# titan.net
KiCad netlist of a schematic drawn in EAGLE
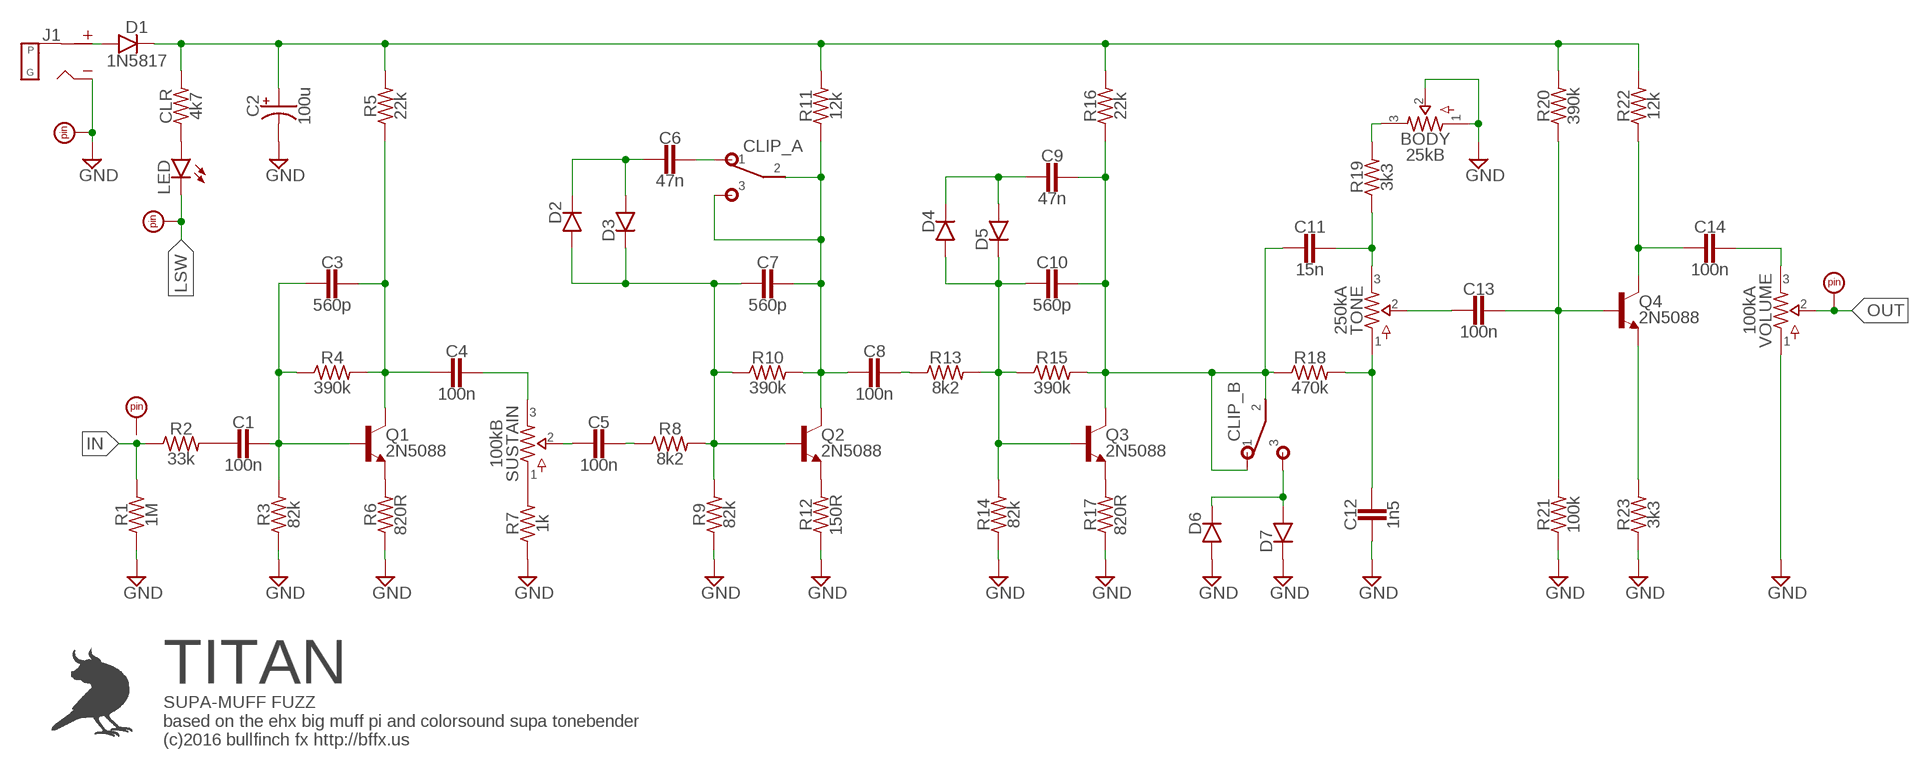
[diagram p0: schematic, sheet 1]

(export (version "E")
  (design (tool "Eeschema 10.0.6"))
  (components
    (comp (ref "BODY")
      (value "25kB")
      (footprint "eagle-import:16MM")
      (libsource (lib "eagle-import") (part "POTS16MM"))
    )
    (comp (ref "C1")
      (value "100n")
      (footprint "eagle-import:050X030_025_2")
      (libsource (lib "eagle-import") (part "CER/FILM2"))
    )
    (comp (ref "C2")
      (value "100u")
      (footprint "eagle-import:050_020_1")
      (libsource (lib "eagle-import") (part "0501"))
    )
    (comp (ref "C3")
      (value "560p")
      (footprint "eagle-import:050X030_025_2")
      (libsource (lib "eagle-import") (part "CER/FILM2"))
    )
    (comp (ref "C4")
      (value "100n")
      (footprint "eagle-import:050X030_025_2")
      (libsource (lib "eagle-import") (part "CER/FILM2"))
    )
    (comp (ref "C5")
      (value "100n")
      (footprint "eagle-import:050X030_025_2")
      (libsource (lib "eagle-import") (part "CER/FILM2"))
    )
    (comp (ref "C6")
      (value "47n")
      (footprint "eagle-import:050X030_025_2")
      (libsource (lib "eagle-import") (part "CER/FILM2"))
    )
    (comp (ref "C7")
      (value "560p")
      (footprint "eagle-import:050X030_025_2")
      (libsource (lib "eagle-import") (part "CER/FILM2"))
    )
    (comp (ref "C8")
      (value "100n")
      (footprint "eagle-import:050X030_025_2")
      (libsource (lib "eagle-import") (part "CER/FILM2"))
    )
    (comp (ref "C9")
      (value "47n")
      (footprint "eagle-import:050X030_025_2")
      (libsource (lib "eagle-import") (part "CER/FILM2"))
    )
    (comp (ref "C10")
      (value "560p")
      (footprint "eagle-import:050X030_025_2")
      (libsource (lib "eagle-import") (part "CER/FILM2"))
    )
    (comp (ref "C11")
      (value "15n")
      (footprint "eagle-import:050X030_025_2")
      (libsource (lib "eagle-import") (part "CER/FILM2"))
    )
    (comp (ref "C12")
      (value "1n5")
      (footprint "eagle-import:050X030_025_2")
      (libsource (lib "eagle-import") (part "CER/FILM2"))
    )
    (comp (ref "C13")
      (value "100n")
      (footprint "eagle-import:050X030_025_2")
      (libsource (lib "eagle-import") (part "CER/FILM2"))
    )
    (comp (ref "C14")
      (value "100n")
      (footprint "eagle-import:050X030_025_2")
      (libsource (lib "eagle-import") (part "CER/FILM2"))
    )
    (comp (ref "CLIP")
      (value "DPDTPADS")
      (footprint "eagle-import:DPDT_PADS")
      (libsource (lib "eagle-import") (part "DPDTPADS"))
    )
    (comp (ref "CLR")
      (value "4k7")
      (footprint "eagle-import:R0207_3")
      (libsource (lib "eagle-import") (part "R_.3B"))
    )
    (comp (ref "D1")
      (value "1N5817")
      (footprint "eagle-import:DO41-3")
      (libsource (lib "eagle-import") (part "DO41.3"))
    )
    (comp (ref "D2")
      (value "DO35.2")
      (footprint "eagle-import:DO35-2")
      (libsource (lib "eagle-import") (part "DO35.2"))
    )
    (comp (ref "D3")
      (value "DO35.2")
      (footprint "eagle-import:DO35-2")
      (libsource (lib "eagle-import") (part "DO35.2"))
    )
    (comp (ref "D4")
      (value "DO35.2")
      (footprint "eagle-import:DO35-2")
      (libsource (lib "eagle-import") (part "DO35.2"))
    )
    (comp (ref "D5")
      (value "DO35.2")
      (footprint "eagle-import:DO35-2")
      (libsource (lib "eagle-import") (part "DO35.2"))
    )
    (comp (ref "D6")
      (value "DO35.2")
      (footprint "eagle-import:DO35-2")
      (libsource (lib "eagle-import") (part "DO35.2"))
    )
    (comp (ref "D7")
      (value "DO35.2")
      (footprint "eagle-import:DO35-2")
      (libsource (lib "eagle-import") (part "DO35.2"))
    )
    (comp (ref "GND")
      (value "PADRND")
      (footprint "eagle-import:ROUND")
      (libsource (lib "eagle-import") (part "PADRND"))
    )
    (comp (ref "IN")
      (value "PADSQR")
      (footprint "eagle-import:SQUARE")
      (libsource (lib "eagle-import") (part "PADSQR"))
    )
    (comp (ref "J1")
      (value "DC_MONO")
      (footprint "eagle-import:DC")
      (libsource (lib "eagle-import") (part "DC_MONO"))
    )
    (comp (ref "LED")
      (value "LEDA")
      (footprint "eagle-import:3MM_A")
      (libsource (lib "eagle-import") (part "LEDA"))
    )
    (comp (ref "LSW")
      (value "PADSQR")
      (footprint "eagle-import:SQUARE")
      (libsource (lib "eagle-import") (part "PADSQR"))
    )
    (comp (ref "OUT")
      (value "PADSQR")
      (footprint "eagle-import:SQUARE")
      (libsource (lib "eagle-import") (part "PADSQR"))
    )
    (comp (ref "Q1")
      (value "2N5088")
      (footprint "eagle-import:TO92-")
      (libsource (lib "eagle-import") (part "2N5088"))
    )
    (comp (ref "Q2")
      (value "2N5088")
      (footprint "eagle-import:TO92-")
      (libsource (lib "eagle-import") (part "2N5088"))
    )
    (comp (ref "Q3")
      (value "2N5088")
      (footprint "eagle-import:TO92-")
      (libsource (lib "eagle-import") (part "2N5088"))
    )
    (comp (ref "Q4")
      (value "2N5088")
      (footprint "eagle-import:TO92-")
      (libsource (lib "eagle-import") (part "2N5088"))
    )
    (comp (ref "R1")
      (value "1M")
      (footprint "eagle-import:R0207_3")
      (libsource (lib "eagle-import") (part "R_.3B"))
    )
    (comp (ref "R2")
      (value "33k")
      (footprint "eagle-import:R0207_3")
      (libsource (lib "eagle-import") (part "R_.3B"))
    )
    (comp (ref "R3")
      (value "82k")
      (footprint "eagle-import:R0207_3")
      (libsource (lib "eagle-import") (part "R_.3B"))
    )
    (comp (ref "R4")
      (value "390k")
      (footprint "eagle-import:R0207_3")
      (libsource (lib "eagle-import") (part "R_.3B"))
    )
    (comp (ref "R5")
      (value "22k")
      (footprint "eagle-import:R0207_3")
      (libsource (lib "eagle-import") (part "R_.3B"))
    )
    (comp (ref "R6")
      (value "820R")
      (footprint "eagle-import:R0207_3")
      (libsource (lib "eagle-import") (part "R_.3B"))
    )
    (comp (ref "R7")
      (value "1k")
      (footprint "eagle-import:R0207_3")
      (libsource (lib "eagle-import") (part "R_.3B"))
    )
    (comp (ref "R8")
      (value "8k2")
      (footprint "eagle-import:R0207_3")
      (libsource (lib "eagle-import") (part "R_.3B"))
    )
    (comp (ref "R9")
      (value "82k")
      (footprint "eagle-import:R0207_3")
      (libsource (lib "eagle-import") (part "R_.3B"))
    )
    (comp (ref "R10")
      (value "390k")
      (footprint "eagle-import:R0207_3")
      (libsource (lib "eagle-import") (part "R_.3B"))
    )
    (comp (ref "R11")
      (value "12k")
      (footprint "eagle-import:R0207_3")
      (libsource (lib "eagle-import") (part "R_.3B"))
    )
    (comp (ref "R12")
      (value "150R")
      (footprint "eagle-import:R0207_3")
      (libsource (lib "eagle-import") (part "R_.3B"))
    )
    (comp (ref "R13")
      (value "8k2")
      (footprint "eagle-import:R0207_3")
      (libsource (lib "eagle-import") (part "R_.3B"))
    )
    (comp (ref "R14")
      (value "82k")
      (footprint "eagle-import:R0207_3")
      (libsource (lib "eagle-import") (part "R_.3B"))
    )
    (comp (ref "R15")
      (value "390k")
      (footprint "eagle-import:R0207_3")
      (libsource (lib "eagle-import") (part "R_.3B"))
    )
    (comp (ref "R16")
      (value "22k")
      (footprint "eagle-import:R0207_3")
      (libsource (lib "eagle-import") (part "R_.3B"))
    )
    (comp (ref "R17")
      (value "820R")
      (footprint "eagle-import:R0207_3")
      (libsource (lib "eagle-import") (part "R_.3B"))
    )
    (comp (ref "R18")
      (value "470k")
      (footprint "eagle-import:R0207_3")
      (libsource (lib "eagle-import") (part "R_.3B"))
    )
    (comp (ref "R19")
      (value "3k3")
      (footprint "eagle-import:R0207_3")
      (libsource (lib "eagle-import") (part "R_.3B"))
    )
    (comp (ref "R20")
      (value "390k")
      (footprint "eagle-import:R0207_3")
      (libsource (lib "eagle-import") (part "R_.3B"))
    )
    (comp (ref "R21")
      (value "100k")
      (footprint "eagle-import:R0207_3")
      (libsource (lib "eagle-import") (part "R_.3B"))
    )
    (comp (ref "R22")
      (value "12k")
      (footprint "eagle-import:R0207_3")
      (libsource (lib "eagle-import") (part "R_.3B"))
    )
    (comp (ref "R23")
      (value "3k3")
      (footprint "eagle-import:R0207_3")
      (libsource (lib "eagle-import") (part "R_.3B"))
    )
    (comp (ref "SUSTAIN")
      (value "100kB")
      (footprint "eagle-import:16MM")
      (libsource (lib "eagle-import") (part "POTS16MM"))
    )
    (comp (ref "TONE")
      (value "250kA")
      (footprint "eagle-import:16MM")
      (libsource (lib "eagle-import") (part "POTS16MM"))
    )
    (comp (ref "VOLUME")
      (value "100kA")
      (footprint "eagle-import:16MM")
      (libsource (lib "eagle-import") (part "POTS16MM"))
    )
  )
  (nets
    (net (code "1") (name "GND") (class "Default")
      (node (ref "BODY") (pin "1") (pinfunction "1_1") (pintype "passive"))
      (node (ref "BODY") (pin "2") (pinfunction "2_2") (pintype "passive"))
      (node (ref "C12") (pin "2") (pinfunction "2_2") (pintype "passive"))
      (node (ref "C2") (pin "-") (pinfunction "-_-") (pintype "passive"))
      (node (ref "D6") (pin "A") (pinfunction "A_A") (pintype "passive"))
      (node (ref "D7") (pin "C") (pinfunction "C_C") (pintype "passive"))
      (node (ref "GND") (pin "1") (pinfunction "P$1_1") (pintype "bidirectional"))
      (node (ref "J1") (pin "S") (pinfunction "SLEEVE_S") (pintype "passive"))
      (node (ref "R1") (pin "1") (pinfunction "1_1") (pintype "passive"))
      (node (ref "R12") (pin "1") (pinfunction "1_1") (pintype "passive"))
      (node (ref "R14") (pin "1") (pinfunction "1_1") (pintype "passive"))
      (node (ref "R17") (pin "1") (pinfunction "1_1") (pintype "passive"))
      (node (ref "R21") (pin "1") (pinfunction "1_1") (pintype "passive"))
      (node (ref "R23") (pin "1") (pinfunction "1_1") (pintype "passive"))
      (node (ref "R3") (pin "1") (pinfunction "1_1") (pintype "passive"))
      (node (ref "R6") (pin "1") (pinfunction "1_1") (pintype "passive"))
      (node (ref "R7") (pin "1") (pinfunction "1_1") (pintype "passive"))
      (node (ref "R9") (pin "1") (pinfunction "1_1") (pintype "passive"))
      (node (ref "VOLUME") (pin "1") (pinfunction "1_1") (pintype "passive"))
    )
    (net (code "2") (name "IN") (class "Default")
      (node (ref "R1") (pin "2") (pinfunction "2_2") (pintype "passive"))
      (node (ref "R2") (pin "1") (pinfunction "1_1") (pintype "passive"))
    )
    (net (code "3") (name "LSW") (class "Default")
      (node (ref "LED") (pin "K") (pinfunction "C_K") (pintype "passive"))
      (node (ref "LSW") (pin "1") (pinfunction "P$1_1") (pintype "bidirectional"))
    )
    (net (code "4") (name "Net-(BODY-Pad3)") (class "Default")
      (node (ref "BODY") (pin "3") (pinfunction "3_3") (pintype "passive"))
      (node (ref "R19") (pin "2") (pinfunction "2_2") (pintype "passive"))
    )
    (net (code "5") (name "Net-(C1-Pad2)") (class "Default")
      (node (ref "C1") (pin "2") (pinfunction "2_2") (pintype "passive"))
      (node (ref "R2") (pin "2") (pinfunction "2_2") (pintype "passive"))
    )
    (net (code "6") (name "Net-(C2-Pad+)") (class "Default")
      (node (ref "C2") (pin "+") (pinfunction "+_+") (pintype "passive"))
      (node (ref "CLR") (pin "2") (pinfunction "2_2") (pintype "passive"))
      (node (ref "D1") (pin "C") (pinfunction "C_C") (pintype "passive"))
      (node (ref "R11") (pin "2") (pinfunction "2_2") (pintype "passive"))
      (node (ref "R16") (pin "2") (pinfunction "2_2") (pintype "passive"))
      (node (ref "R20") (pin "2") (pinfunction "2_2") (pintype "passive"))
      (node (ref "R22") (pin "2") (pinfunction "2_2") (pintype "passive"))
      (node (ref "R5") (pin "2") (pinfunction "2_2") (pintype "passive"))
    )
    (net (code "7") (name "Net-(C4-Pad1)") (class "Default")
      (node (ref "C4") (pin "1") (pinfunction "1_1") (pintype "passive"))
      (node (ref "SUSTAIN") (pin "3") (pinfunction "3_3") (pintype "passive"))
    )
    (net (code "8") (name "Net-(C5-Pad1)") (class "Default")
      (node (ref "C5") (pin "1") (pinfunction "1_1") (pintype "passive"))
      (node (ref "R8") (pin "1") (pinfunction "1_1") (pintype "passive"))
    )
    (net (code "9") (name "Net-(C5-Pad2)") (class "Default")
      (node (ref "C5") (pin "2") (pinfunction "2_2") (pintype "passive"))
      (node (ref "SUSTAIN") (pin "2") (pinfunction "2_2") (pintype "passive"))
    )
    (net (code "10") (name "Net-(C6-Pad2)") (class "Default")
      (node (ref "C6") (pin "2") (pinfunction "2_2") (pintype "passive"))
      (node (ref "D2") (pin "C") (pinfunction "C_C") (pintype "passive"))
      (node (ref "D3") (pin "A") (pinfunction "A_A") (pintype "passive"))
    )
    (net (code "11") (name "Net-(C8-Pad1)") (class "Default")
      (node (ref "C8") (pin "1") (pinfunction "1_1") (pintype "passive"))
      (node (ref "R13") (pin "1") (pinfunction "1_1") (pintype "passive"))
    )
    (net (code "12") (name "Net-(C9-Pad2)") (class "Default")
      (node (ref "C9") (pin "2") (pinfunction "2_2") (pintype "passive"))
      (node (ref "D4") (pin "C") (pinfunction "C_C") (pintype "passive"))
      (node (ref "D5") (pin "A") (pinfunction "A_A") (pintype "passive"))
    )
    (net (code "13") (name "Net-(C11-Pad1)") (class "Default")
      (node (ref "C11") (pin "1") (pinfunction "1_1") (pintype "passive"))
      (node (ref "R19") (pin "1") (pinfunction "1_1") (pintype "passive"))
      (node (ref "TONE") (pin "3") (pinfunction "3_3") (pintype "passive"))
    )
    (net (code "14") (name "Net-(C12-Pad1)") (class "Default")
      (node (ref "C12") (pin "1") (pinfunction "1_1") (pintype "passive"))
      (node (ref "R18") (pin "2") (pinfunction "2_2") (pintype "passive"))
      (node (ref "TONE") (pin "1") (pinfunction "1_1") (pintype "passive"))
    )
    (net (code "15") (name "Net-(C13-Pad2)") (class "Default")
      (node (ref "C13") (pin "2") (pinfunction "2_2") (pintype "passive"))
      (node (ref "TONE") (pin "2") (pinfunction "2_2") (pintype "passive"))
    )
    (net (code "16") (name "Net-(C14-Pad1)") (class "Default")
      (node (ref "C14") (pin "1") (pinfunction "1_1") (pintype "passive"))
      (node (ref "VOLUME") (pin "3") (pinfunction "3_3") (pintype "passive"))
    )
    (net (code "17") (name "Net-(CLIPA-1)") (class "Default")
      (node (ref "C6") (pin "1") (pinfunction "1_1") (pintype "passive"))
      (node (ref "CLIP") (pin "P$1") (pinfunction "1_P$1") (pintype "passive"))
    )
    (net (code "18") (name "Net-(CLIPA-2)") (class "Default")
      (node (ref "C7") (pin "1") (pinfunction "1_1") (pintype "passive"))
      (node (ref "C8") (pin "2") (pinfunction "2_2") (pintype "passive"))
      (node (ref "CLIP") (pin "P$2") (pinfunction "2_P$2") (pintype "passive"))
      (node (ref "CLIP") (pin "P$3") (pinfunction "3_P$3") (pintype "passive"))
      (node (ref "Q2") (pin "1") (pinfunction "C_1") (pintype "passive"))
      (node (ref "R10") (pin "2") (pinfunction "2_2") (pintype "passive"))
      (node (ref "R11") (pin "1") (pinfunction "1_1") (pintype "passive"))
    )
    (net (code "19") (name "Net-(CLIPB-1)") (class "Default")
      (node (ref "C10") (pin "1") (pinfunction "1_1") (pintype "passive"))
      (node (ref "C11") (pin "2") (pinfunction "2_2") (pintype "passive"))
      (node (ref "C9") (pin "1") (pinfunction "1_1") (pintype "passive"))
      (node (ref "CLIP") (pin "P$4") (pinfunction "1_P$4") (pintype "passive"))
      (node (ref "CLIP") (pin "P$5") (pinfunction "2_P$5") (pintype "passive"))
      (node (ref "Q3") (pin "1") (pinfunction "C_1") (pintype "passive"))
      (node (ref "R15") (pin "2") (pinfunction "2_2") (pintype "passive"))
      (node (ref "R16") (pin "1") (pinfunction "1_1") (pintype "passive"))
      (node (ref "R18") (pin "1") (pinfunction "1_1") (pintype "passive"))
    )
    (net (code "20") (name "Net-(CLIPB-3)") (class "Default")
      (node (ref "CLIP") (pin "P$6") (pinfunction "3_P$6") (pintype "passive"))
      (node (ref "D6") (pin "C") (pinfunction "C_C") (pintype "passive"))
      (node (ref "D7") (pin "A") (pinfunction "A_A") (pintype "passive"))
    )
    (net (code "21") (name "Net-(CLR-Pad1)") (class "Default")
      (node (ref "CLR") (pin "1") (pinfunction "1_1") (pintype "passive"))
      (node (ref "LED") (pin "A") (pinfunction "A_A") (pintype "passive"))
    )
    (net (code "22") (name "Net-(J1-TIP)") (class "Default")
      (node (ref "D1") (pin "A") (pinfunction "A_A") (pintype "passive"))
      (node (ref "J1") (pin "T") (pinfunction "TIP_T") (pintype "passive"))
    )
    (net (code "23") (name "Net-(Q1-B)") (class "Default")
      (node (ref "C1") (pin "1") (pinfunction "1_1") (pintype "passive"))
      (node (ref "C3") (pin "2") (pinfunction "2_2") (pintype "passive"))
      (node (ref "Q1") (pin "2") (pinfunction "B_2") (pintype "passive"))
      (node (ref "R3") (pin "2") (pinfunction "2_2") (pintype "passive"))
      (node (ref "R4") (pin "1") (pinfunction "1_1") (pintype "passive"))
    )
    (net (code "24") (name "Net-(Q1-C)") (class "Default")
      (node (ref "C3") (pin "1") (pinfunction "1_1") (pintype "passive"))
      (node (ref "C4") (pin "2") (pinfunction "2_2") (pintype "passive"))
      (node (ref "Q1") (pin "1") (pinfunction "C_1") (pintype "passive"))
      (node (ref "R4") (pin "2") (pinfunction "2_2") (pintype "passive"))
      (node (ref "R5") (pin "1") (pinfunction "1_1") (pintype "passive"))
    )
    (net (code "25") (name "Net-(Q1-E)") (class "Default")
      (node (ref "Q1") (pin "3") (pinfunction "E_3") (pintype "passive"))
      (node (ref "R6") (pin "2") (pinfunction "2_2") (pintype "passive"))
    )
    (net (code "26") (name "Net-(Q2-B)") (class "Default")
      (node (ref "C7") (pin "2") (pinfunction "2_2") (pintype "passive"))
      (node (ref "D2") (pin "A") (pinfunction "A_A") (pintype "passive"))
      (node (ref "D3") (pin "C") (pinfunction "C_C") (pintype "passive"))
      (node (ref "Q2") (pin "2") (pinfunction "B_2") (pintype "passive"))
      (node (ref "R10") (pin "1") (pinfunction "1_1") (pintype "passive"))
      (node (ref "R8") (pin "2") (pinfunction "2_2") (pintype "passive"))
      (node (ref "R9") (pin "2") (pinfunction "2_2") (pintype "passive"))
    )
    (net (code "27") (name "Net-(Q2-E)") (class "Default")
      (node (ref "Q2") (pin "3") (pinfunction "E_3") (pintype "passive"))
      (node (ref "R12") (pin "2") (pinfunction "2_2") (pintype "passive"))
    )
    (net (code "28") (name "Net-(Q3-B)") (class "Default")
      (node (ref "C10") (pin "2") (pinfunction "2_2") (pintype "passive"))
      (node (ref "D4") (pin "A") (pinfunction "A_A") (pintype "passive"))
      (node (ref "D5") (pin "C") (pinfunction "C_C") (pintype "passive"))
      (node (ref "Q3") (pin "2") (pinfunction "B_2") (pintype "passive"))
      (node (ref "R13") (pin "2") (pinfunction "2_2") (pintype "passive"))
      (node (ref "R14") (pin "2") (pinfunction "2_2") (pintype "passive"))
      (node (ref "R15") (pin "1") (pinfunction "1_1") (pintype "passive"))
    )
    (net (code "29") (name "Net-(Q3-E)") (class "Default")
      (node (ref "Q3") (pin "3") (pinfunction "E_3") (pintype "passive"))
      (node (ref "R17") (pin "2") (pinfunction "2_2") (pintype "passive"))
    )
    (net (code "30") (name "Net-(Q4-B)") (class "Default")
      (node (ref "C13") (pin "1") (pinfunction "1_1") (pintype "passive"))
      (node (ref "Q4") (pin "2") (pinfunction "B_2") (pintype "passive"))
      (node (ref "R20") (pin "1") (pinfunction "1_1") (pintype "passive"))
      (node (ref "R21") (pin "2") (pinfunction "2_2") (pintype "passive"))
    )
    (net (code "31") (name "Net-(Q4-C)") (class "Default")
      (node (ref "C14") (pin "2") (pinfunction "2_2") (pintype "passive"))
      (node (ref "Q4") (pin "1") (pinfunction "C_1") (pintype "passive"))
      (node (ref "R22") (pin "1") (pinfunction "1_1") (pintype "passive"))
    )
    (net (code "32") (name "Net-(Q4-E)") (class "Default")
      (node (ref "Q4") (pin "3") (pinfunction "E_3") (pintype "passive"))
      (node (ref "R23") (pin "2") (pinfunction "2_2") (pintype "passive"))
    )
    (net (code "33") (name "Net-(R7-Pad2)") (class "Default")
      (node (ref "R7") (pin "2") (pinfunction "2_2") (pintype "passive"))
      (node (ref "SUSTAIN") (pin "1") (pinfunction "1_1") (pintype "passive"))
    )
    (net (code "34") (name "OUT") (class "Default")
      (node (ref "OUT") (pin "1") (pinfunction "P$1_1") (pintype "bidirectional"))
      (node (ref "VOLUME") (pin "2") (pinfunction "2_2") (pintype "passive"))
    )
    (net (code "35") (name "unconnected-(IN-P$1-Pad1)") (class "Default")
      (node (ref "IN") (pin "1") (pinfunction "P$1_1") (pintype "bidirectional"))
    )
  )
)
